# hs-256-expansion.net
KiCad netlist of a schematic drawn in EAGLE
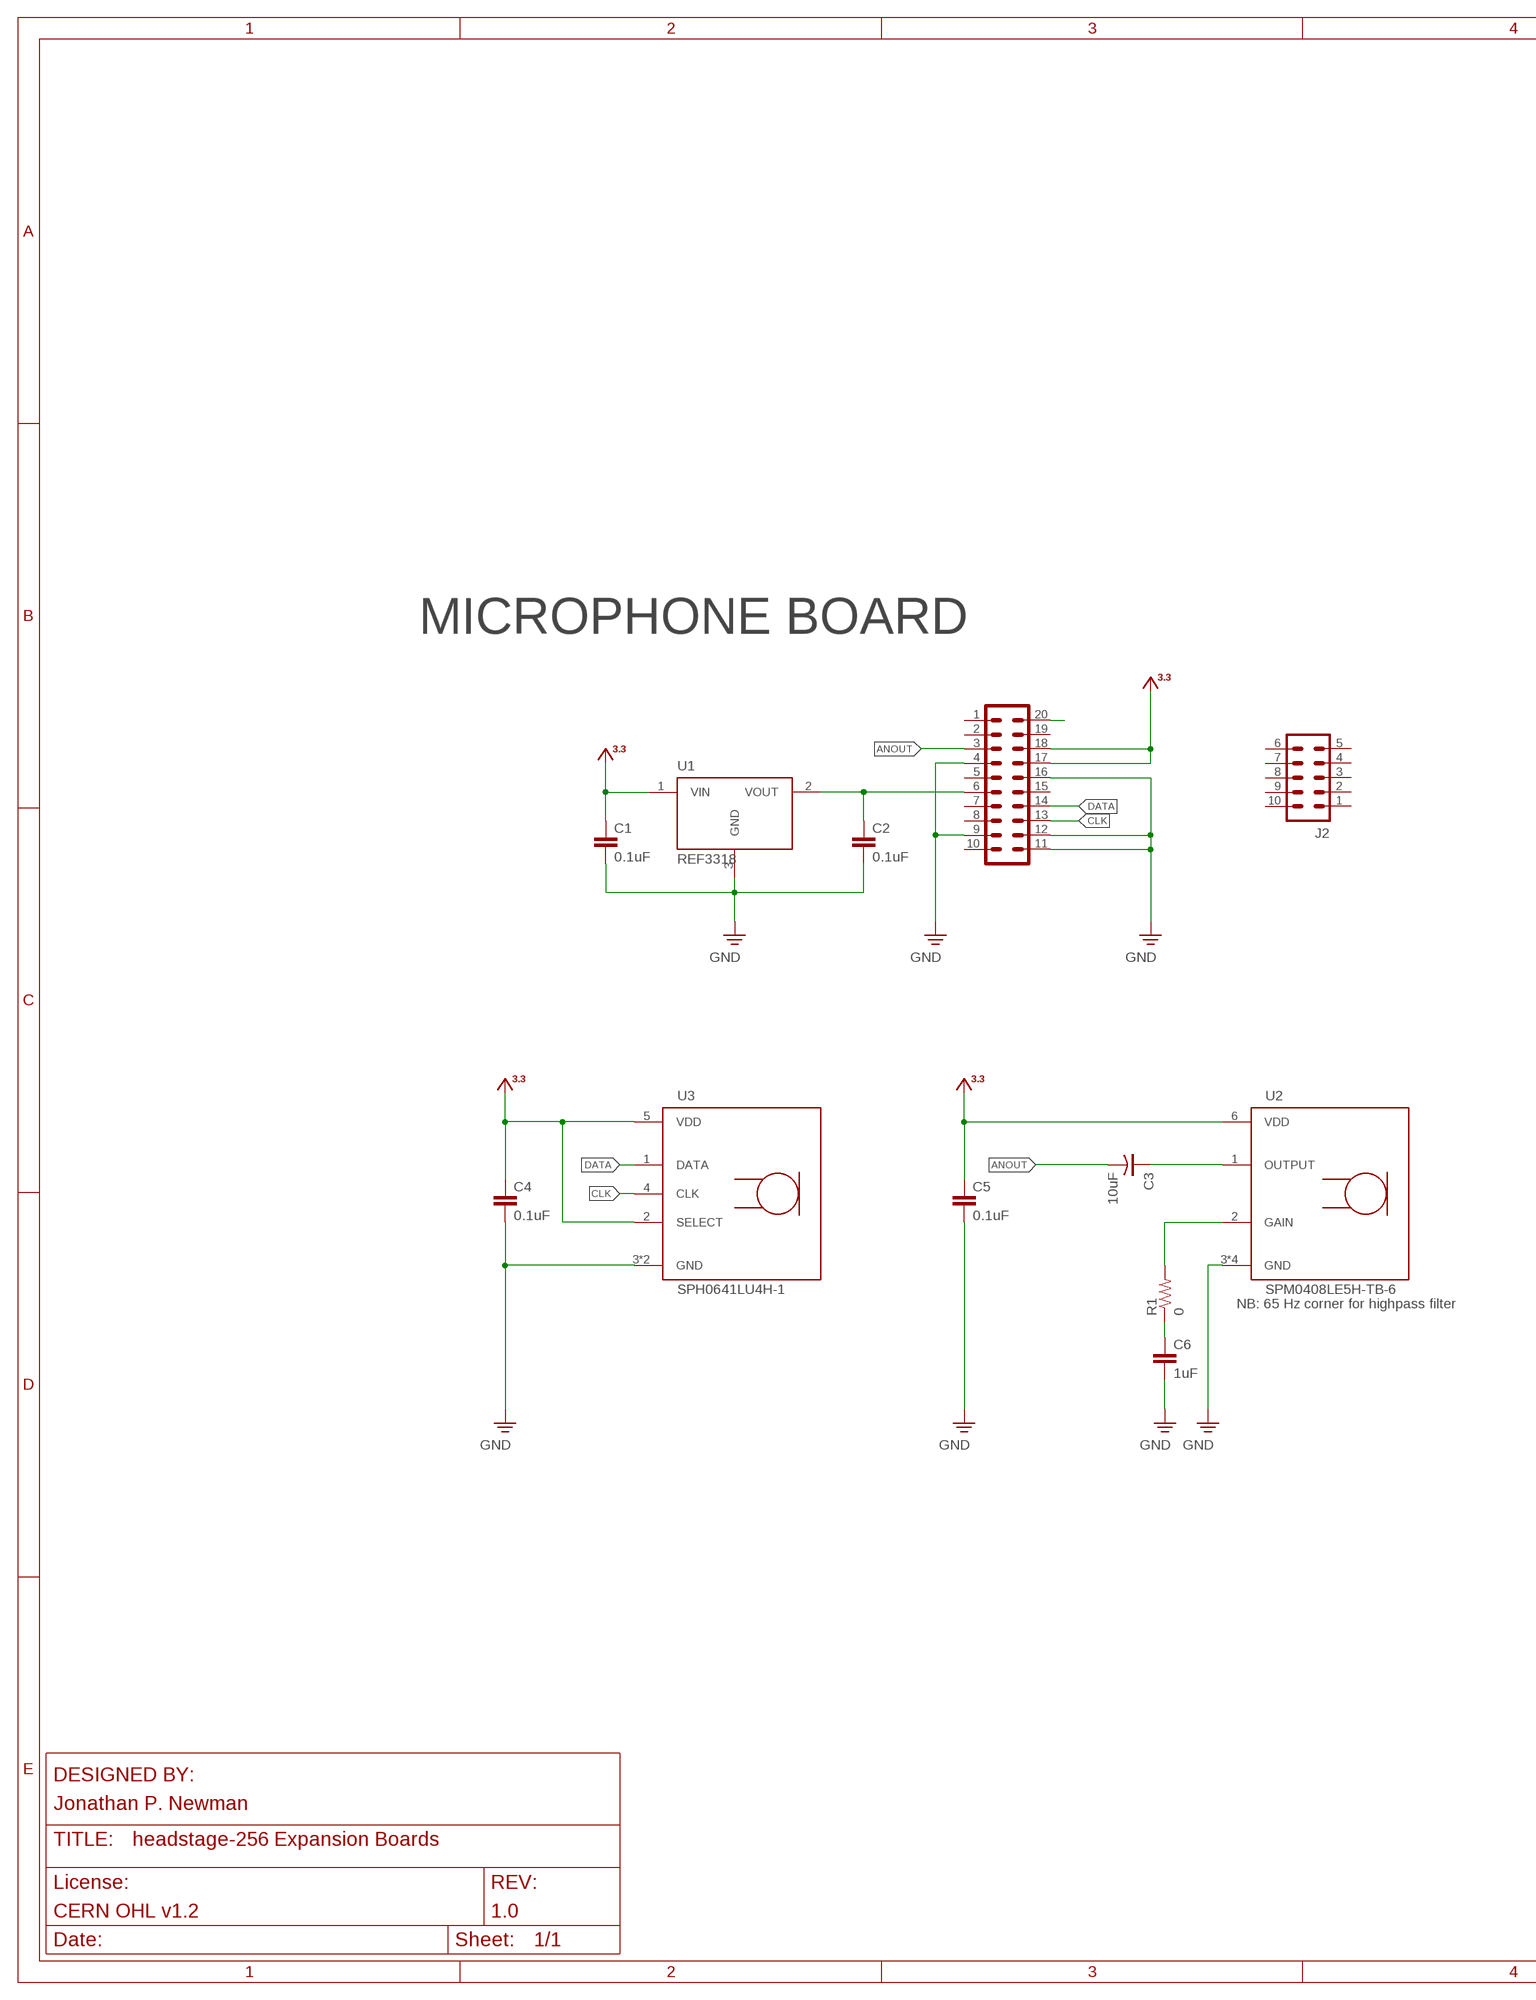
[diagram p0: schematic, sheet 1, part 1 of 2]
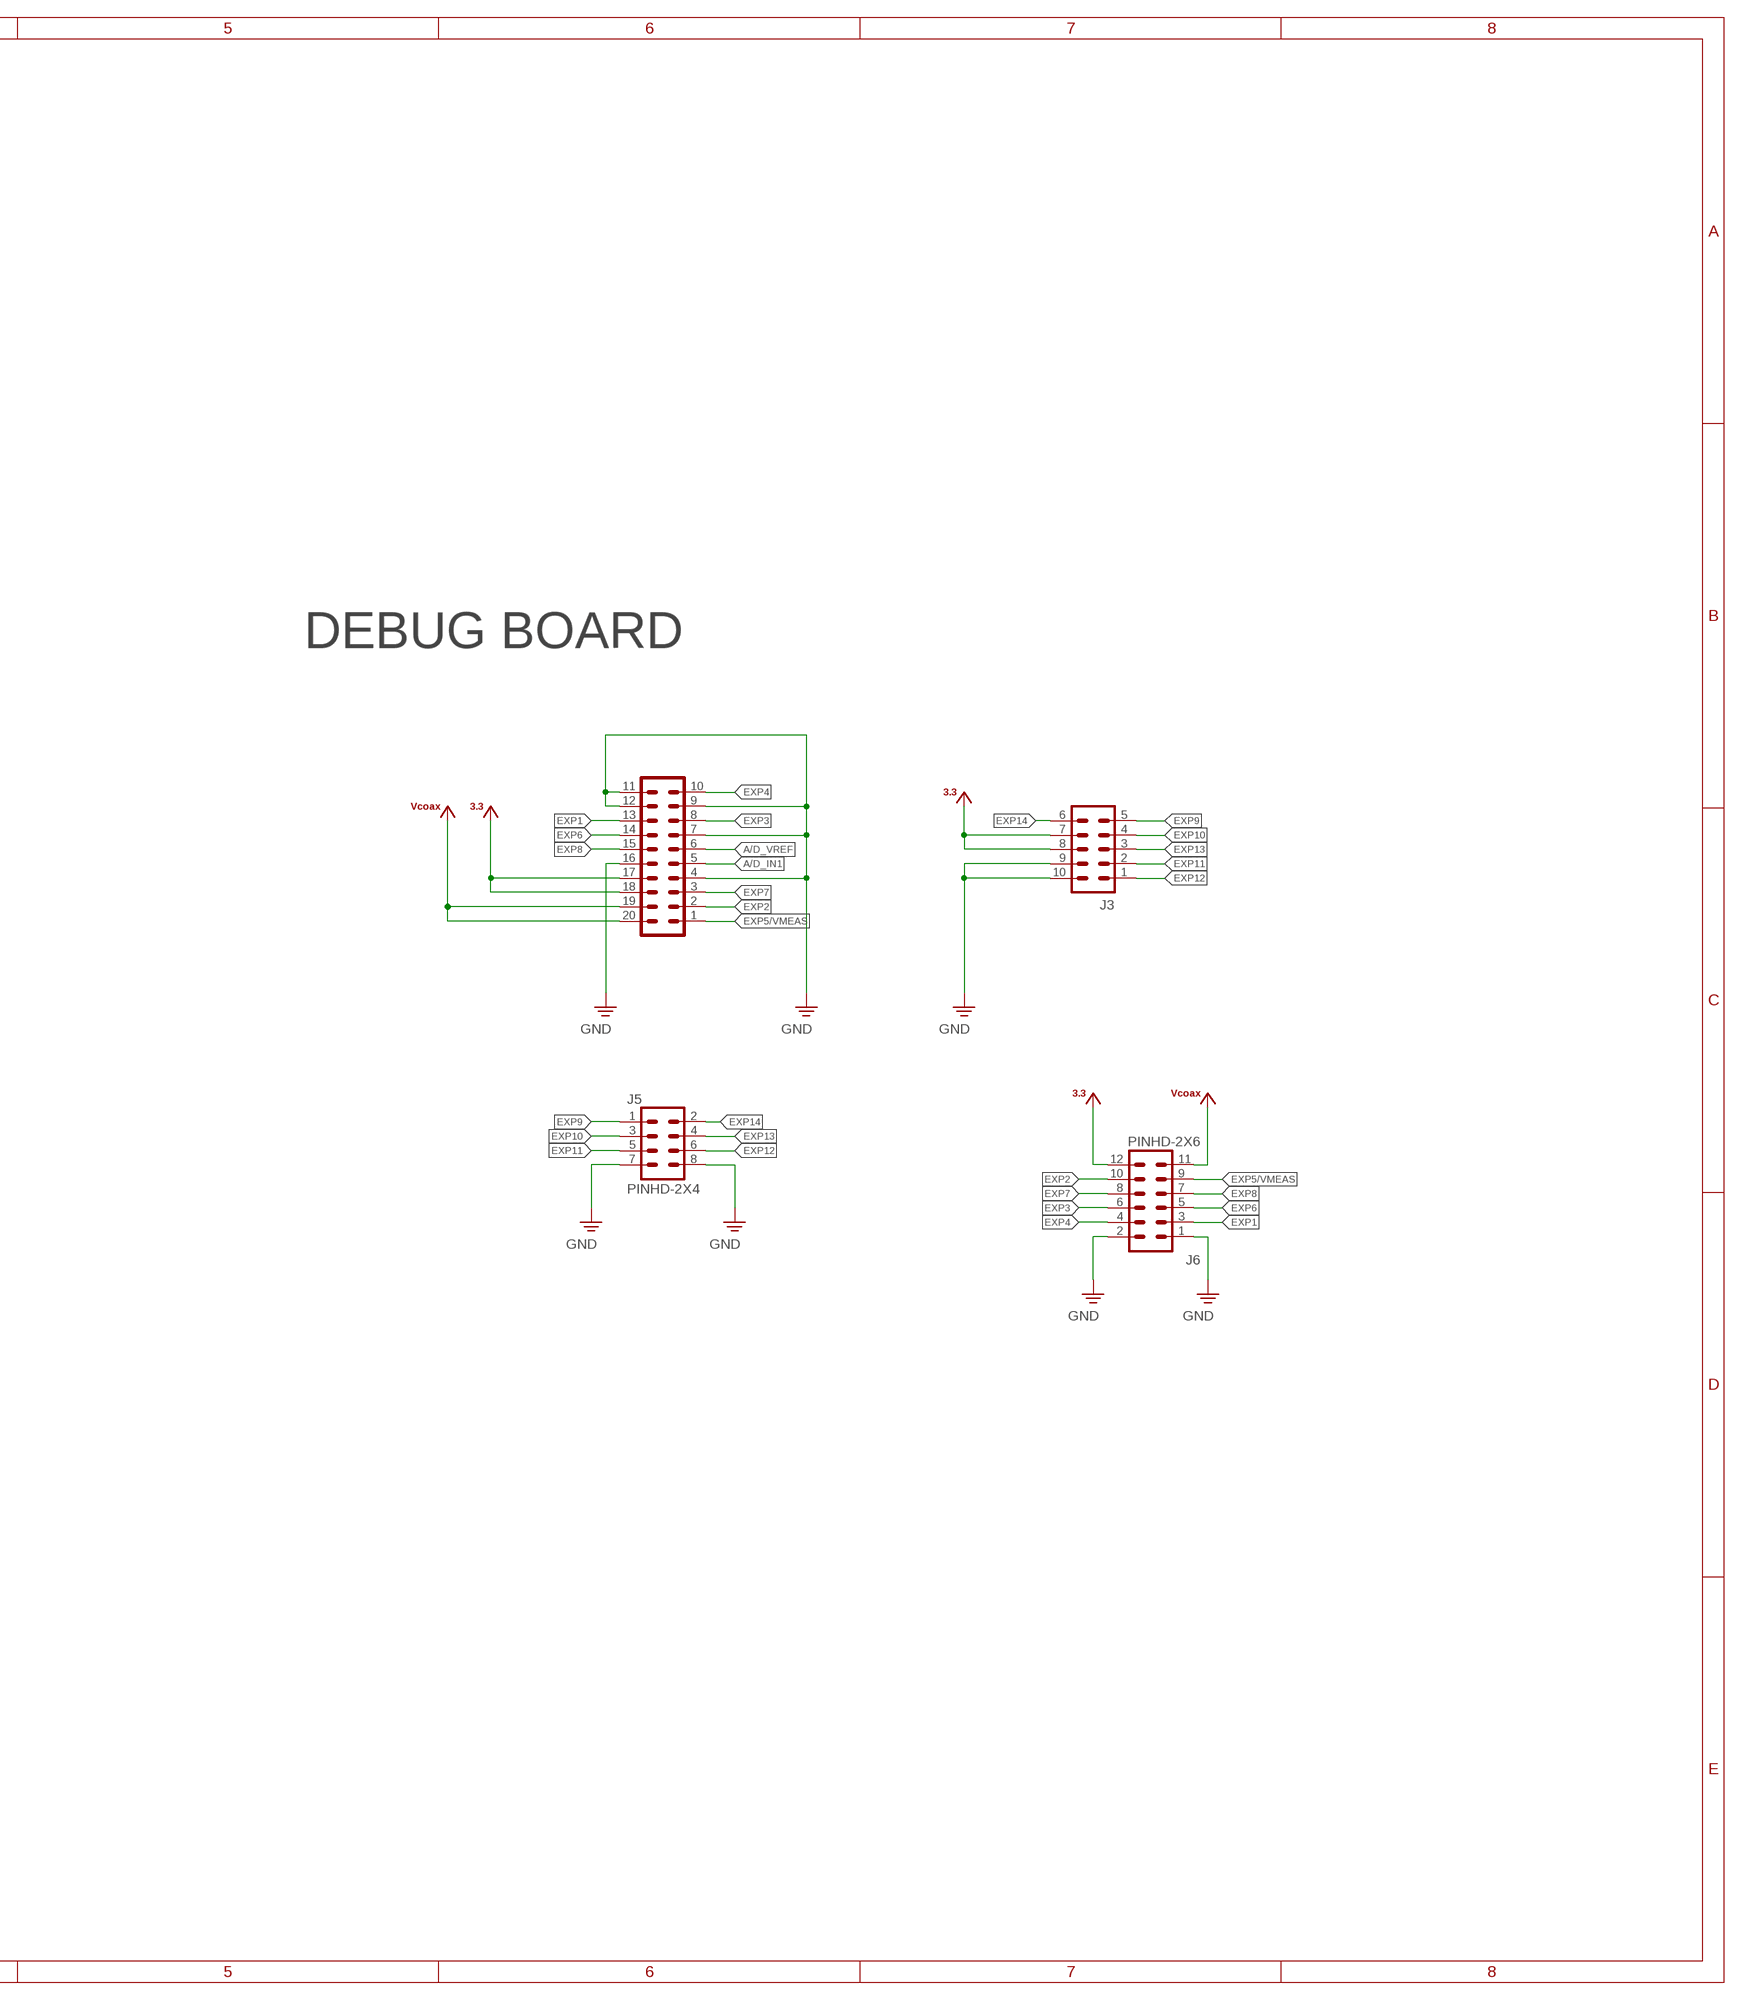
[diagram p1: schematic, sheet 1, part 2 of 2]

(export (version "E")
  (design (tool "Eeschema 10.0.6"))
  (components
    (comp (ref "C1")
      (value "0.1uF")
      (footprint "eagle-import:0402")
      (libsource (lib "eagle-import") (part "C_0402"))
    )
    (comp (ref "C2")
      (value "0.1uF")
      (footprint "eagle-import:0402")
      (libsource (lib "eagle-import") (part "C_0402"))
    )
    (comp (ref "C3")
      (value "10uF")
      (footprint "eagle-import:0805-POL")
      (libsource (lib "eagle-import") (part "C-POL_0805"))
    )
    (comp (ref "C4")
      (value "0.1uF")
      (footprint "eagle-import:0402")
      (libsource (lib "eagle-import") (part "C_0402"))
    )
    (comp (ref "C5")
      (value "0.1uF")
      (footprint "eagle-import:0402")
      (libsource (lib "eagle-import") (part "C_0402"))
    )
    (comp (ref "C6")
      (value "1uF")
      (footprint "eagle-import:0402")
      (libsource (lib "eagle-import") (part "C_0402"))
    )
    (comp (ref "J1")
      (value "PINHD-2X10_DF40-20REC")
      (footprint "eagle-import:DF40-20REC")
      (libsource (lib "eagle-import") (part "PINHD-2X10_DF40-20REC"))
    )
    (comp (ref "J2")
      (value "PINHD-2X5_DF40-REC")
      (footprint "eagle-import:DF40-10REC")
      (libsource (lib "eagle-import") (part "PINHD-2X5_DF40-REC"))
    )
    (comp (ref "J3")
      (value "PINHD-2X5_DF40-REC")
      (footprint "eagle-import:DF40-10REC")
      (libsource (lib "eagle-import") (part "PINHD-2X5_DF40-REC"))
    )
    (comp (ref "J4")
      (value "PINHD-2X10_DF40-20REC")
      (footprint "eagle-import:DF40-20REC")
      (libsource (lib "eagle-import") (part "PINHD-2X10_DF40-20REC"))
    )
    (comp (ref "J5")
      (value "PINHD-2X4")
      (footprint "eagle-import:2X04-BIG")
      (libsource (lib "eagle-import") (part "PINHD-2X4"))
    )
    (comp (ref "J6")
      (value "PINHD-2X6")
      (footprint "eagle-import:2X06-BIG")
      (libsource (lib "eagle-import") (part "PINHD-2X6"))
    )
    (comp (ref "R1")
      (value "0")
      (footprint "eagle-import:0402")
      (libsource (lib "eagle-import") (part "R_0402"))
    )
    (comp (ref "U1")
      (value "REF3318")
      (footprint "eagle-import:SOT23")
      (libsource (lib "eagle-import") (part "VREF_SOT"))
    )
    (comp (ref "U2")
      (value "SPM0408LE5H-TB-6")
      (footprint "eagle-import:KNOWLES-SPM")
      (libsource (lib "eagle-import") (part "MICROPHONE-AN_SPM"))
    )
    (comp (ref "U3")
      (value "SPH0641LU4H-1")
      (footprint "eagle-import:KNOWLES-SPH")
      (libsource (lib "eagle-import") (part "MICROPHONE-PCM_SPH"))
    )
  )
  (nets
    (net (code "1") (name "+3V3") (class "Default")
      (node (ref "C1") (pin "1") (pinfunction "1_1") (pintype "passive"))
      (node (ref "C4") (pin "1") (pinfunction "1_1") (pintype "passive"))
      (node (ref "C5") (pin "1") (pinfunction "1_1") (pintype "passive"))
      (node (ref "J1") (pin "17") (pinfunction "17_17") (pintype "bidirectional"))
      (node (ref "J1") (pin "18") (pinfunction "18_18") (pintype "bidirectional"))
      (node (ref "J3") (pin "7") (pinfunction "8_7") (pintype "passive"))
      (node (ref "J3") (pin "8") (pinfunction "6_8") (pintype "passive"))
      (node (ref "J4") (pin "17") (pinfunction "17_17") (pintype "bidirectional"))
      (node (ref "J4") (pin "18") (pinfunction "18_18") (pintype "bidirectional"))
      (node (ref "J6") (pin "12") (pinfunction "12_12") (pintype "passive"))
      (node (ref "U1") (pin "1") (pinfunction "VIN_1") (pintype "input"))
      (node (ref "U2") (pin "6") (pinfunction "VDD_6") (pintype "power_in"))
      (node (ref "U3") (pin "2") (pinfunction "SELECT_2") (pintype "input"))
      (node (ref "U3") (pin "5") (pinfunction "VDD_5") (pintype "bidirectional"))
    )
    (net (code "2") (name "+VCOAX") (class "Default")
      (node (ref "J4") (pin "19") (pinfunction "19_19") (pintype "bidirectional"))
      (node (ref "J4") (pin "20") (pinfunction "20_20") (pintype "bidirectional"))
      (node (ref "J6") (pin "11") (pinfunction "11_11") (pintype "passive"))
    )
    (net (code "3") (name "ANOUT") (class "Default")
      (node (ref "C3") (pin "C") (pinfunction "-_C") (pintype "passive"))
      (node (ref "J1") (pin "3") (pinfunction "3_3") (pintype "bidirectional"))
    )
    (net (code "4") (name "A{slash}D_IN1") (class "Default")
      (node (ref "J4") (pin "5") (pinfunction "5_5") (pintype "bidirectional"))
    )
    (net (code "5") (name "A{slash}D_VREF") (class "Default")
      (node (ref "J4") (pin "6") (pinfunction "6_6") (pintype "bidirectional"))
    )
    (net (code "6") (name "CLK") (class "Default")
      (node (ref "J1") (pin "13") (pinfunction "13_13") (pintype "bidirectional"))
      (node (ref "U3") (pin "4") (pinfunction "CLK_4") (pintype "input"))
    )
    (net (code "7") (name "DATA") (class "Default")
      (node (ref "J1") (pin "14") (pinfunction "14_14") (pintype "bidirectional"))
      (node (ref "U3") (pin "1") (pinfunction "DATA_1") (pintype "output"))
    )
    (net (code "8") (name "EXP1") (class "Default")
      (node (ref "J4") (pin "13") (pinfunction "13_13") (pintype "bidirectional"))
      (node (ref "J6") (pin "3") (pinfunction "3_3") (pintype "passive"))
    )
    (net (code "9") (name "EXP2") (class "Default")
      (node (ref "J4") (pin "2") (pinfunction "2_2") (pintype "bidirectional"))
      (node (ref "J6") (pin "10") (pinfunction "10_10") (pintype "passive"))
    )
    (net (code "10") (name "EXP3") (class "Default")
      (node (ref "J4") (pin "8") (pinfunction "8_8") (pintype "bidirectional"))
      (node (ref "J6") (pin "6") (pinfunction "6_6") (pintype "passive"))
    )
    (net (code "11") (name "EXP4") (class "Default")
      (node (ref "J4") (pin "10") (pinfunction "10_10") (pintype "bidirectional"))
      (node (ref "J6") (pin "4") (pinfunction "4_4") (pintype "passive"))
    )
    (net (code "12") (name "EXP5{slash}VMEAS") (class "Default")
      (node (ref "J4") (pin "1") (pinfunction "1_1") (pintype "bidirectional"))
      (node (ref "J6") (pin "9") (pinfunction "9_9") (pintype "passive"))
    )
    (net (code "13") (name "EXP6") (class "Default")
      (node (ref "J4") (pin "14") (pinfunction "14_14") (pintype "bidirectional"))
      (node (ref "J6") (pin "5") (pinfunction "5_5") (pintype "passive"))
    )
    (net (code "14") (name "EXP7") (class "Default")
      (node (ref "J4") (pin "3") (pinfunction "3_3") (pintype "bidirectional"))
      (node (ref "J6") (pin "8") (pinfunction "8_8") (pintype "passive"))
    )
    (net (code "15") (name "EXP8") (class "Default")
      (node (ref "J4") (pin "15") (pinfunction "15_15") (pintype "bidirectional"))
      (node (ref "J6") (pin "7") (pinfunction "7_7") (pintype "passive"))
    )
    (net (code "16") (name "EXP9") (class "Default")
      (node (ref "J3") (pin "5") (pinfunction "9_5") (pintype "passive"))
      (node (ref "J5") (pin "1") (pinfunction "1_1") (pintype "passive"))
    )
    (net (code "17") (name "EXP10") (class "Default")
      (node (ref "J3") (pin "4") (pinfunction "7_4") (pintype "passive"))
      (node (ref "J5") (pin "3") (pinfunction "3_3") (pintype "passive"))
    )
    (net (code "18") (name "EXP11") (class "Default")
      (node (ref "J3") (pin "2") (pinfunction "3_2") (pintype "passive"))
      (node (ref "J5") (pin "5") (pinfunction "5_5") (pintype "passive"))
    )
    (net (code "19") (name "EXP12") (class "Default")
      (node (ref "J3") (pin "1") (pinfunction "1_1") (pintype "passive"))
      (node (ref "J5") (pin "6") (pinfunction "6_6") (pintype "passive"))
    )
    (net (code "20") (name "EXP13") (class "Default")
      (node (ref "J3") (pin "3") (pinfunction "5_3") (pintype "passive"))
      (node (ref "J5") (pin "4") (pinfunction "4_4") (pintype "passive"))
    )
    (net (code "21") (name "EXP14") (class "Default")
      (node (ref "J3") (pin "6") (pinfunction "10_6") (pintype "passive"))
      (node (ref "J5") (pin "2") (pinfunction "2_2") (pintype "passive"))
    )
    (net (code "22") (name "GND") (class "Default")
      (node (ref "C1") (pin "2") (pinfunction "2_2") (pintype "passive"))
      (node (ref "C2") (pin "2") (pinfunction "2_2") (pintype "passive"))
      (node (ref "C4") (pin "2") (pinfunction "2_2") (pintype "passive"))
      (node (ref "C5") (pin "2") (pinfunction "2_2") (pintype "passive"))
      (node (ref "C6") (pin "2") (pinfunction "2_2") (pintype "passive"))
      (node (ref "J1") (pin "11") (pinfunction "11_11") (pintype "bidirectional"))
      (node (ref "J1") (pin "12") (pinfunction "12_12") (pintype "bidirectional"))
      (node (ref "J1") (pin "16") (pinfunction "16_16") (pintype "bidirectional"))
      (node (ref "J1") (pin "4") (pinfunction "4_4") (pintype "bidirectional"))
      (node (ref "J1") (pin "9") (pinfunction "9_9") (pintype "bidirectional"))
      (node (ref "J3") (pin "10") (pinfunction "2_10") (pintype "passive"))
      (node (ref "J3") (pin "9") (pinfunction "4_9") (pintype "passive"))
      (node (ref "J4") (pin "11") (pinfunction "11_11") (pintype "bidirectional"))
      (node (ref "J4") (pin "12") (pinfunction "12_12") (pintype "bidirectional"))
      (node (ref "J4") (pin "16") (pinfunction "16_16") (pintype "bidirectional"))
      (node (ref "J4") (pin "4") (pinfunction "4_4") (pintype "bidirectional"))
      (node (ref "J4") (pin "7") (pinfunction "7_7") (pintype "bidirectional"))
      (node (ref "J4") (pin "9") (pinfunction "9_9") (pintype "bidirectional"))
      (node (ref "J5") (pin "7") (pinfunction "7_7") (pintype "passive"))
      (node (ref "J5") (pin "8") (pinfunction "8_8") (pintype "passive"))
      (node (ref "J6") (pin "1") (pinfunction "1_1") (pintype "passive"))
      (node (ref "J6") (pin "2") (pinfunction "2_2") (pintype "passive"))
      (node (ref "U1") (pin "3") (pinfunction "GND_3") (pintype "power_in"))
      (node (ref "U2") (pin "3") (pinfunction "GND_3") (pintype "power_in"))
      (node (ref "U2") (pin "4") (pinfunction "GND_4") (pintype "power_in"))
      (node (ref "U2") (pin "5") (pinfunction "GND_5") (pintype "power_in"))
      (node (ref "U2") (pin "7") (pinfunction "GND_7") (pintype "power_in"))
      (node (ref "U3") (pin "3") (pinfunction "GND_3") (pintype "bidirectional"))
      (node (ref "U3") (pin "6") (pinfunction "GND_6") (pintype "bidirectional"))
    )
    (net (code "23") (name "Net-(C3-+)") (class "Default")
      (node (ref "C3") (pin "A") (pinfunction "+_A") (pintype "passive"))
      (node (ref "U2") (pin "1") (pinfunction "OUTPUT_1") (pintype "output"))
    )
    (net (code "24") (name "Net-(C6-Pad1)") (class "Default")
      (node (ref "C6") (pin "1") (pinfunction "1_1") (pintype "passive"))
      (node (ref "R1") (pin "1") (pinfunction "1_1") (pintype "passive"))
    )
    (net (code "25") (name "Net-(U1-VOUT)") (class "Default")
      (node (ref "C2") (pin "1") (pinfunction "1_1") (pintype "passive"))
      (node (ref "J1") (pin "6") (pinfunction "6_6") (pintype "bidirectional"))
      (node (ref "U1") (pin "2") (pinfunction "VOUT_2") (pintype "output"))
    )
    (net (code "26") (name "Net-(U2-GAIN)") (class "Default")
      (node (ref "R1") (pin "2") (pinfunction "2_2") (pintype "passive"))
      (node (ref "U2") (pin "2") (pinfunction "GAIN_2") (pintype "input"))
    )
    (net (code "27") (name "unconnected-(J1-Pad1)") (class "Default")
      (node (ref "J1") (pin "1") (pinfunction "1_1") (pintype "bidirectional"))
    )
    (net (code "28") (name "unconnected-(J1-Pad2)") (class "Default")
      (node (ref "J1") (pin "2") (pinfunction "2_2") (pintype "bidirectional"))
    )
    (net (code "29") (name "unconnected-(J1-Pad5)") (class "Default")
      (node (ref "J1") (pin "5") (pinfunction "5_5") (pintype "bidirectional"))
    )
    (net (code "30") (name "unconnected-(J1-Pad7)") (class "Default")
      (node (ref "J1") (pin "7") (pinfunction "7_7") (pintype "bidirectional"))
    )
    (net (code "31") (name "unconnected-(J1-Pad8)") (class "Default")
      (node (ref "J1") (pin "8") (pinfunction "8_8") (pintype "bidirectional"))
    )
    (net (code "32") (name "unconnected-(J1-Pad10)") (class "Default")
      (node (ref "J1") (pin "10") (pinfunction "10_10") (pintype "bidirectional"))
    )
    (net (code "33") (name "unconnected-(J1-Pad15)") (class "Default")
      (node (ref "J1") (pin "15") (pinfunction "15_15") (pintype "bidirectional"))
    )
    (net (code "34") (name "unconnected-(J1-Pad19)") (class "Default")
      (node (ref "J1") (pin "19") (pinfunction "19_19") (pintype "bidirectional"))
    )
    (net (code "35") (name "unconnected-(J1-Pad20)") (class "Default")
      (node (ref "J1") (pin "20") (pinfunction "20_20") (pintype "bidirectional"))
    )
    (net (code "36") (name "unconnected-(J2-2-Pad10)") (class "Default")
      (node (ref "J2") (pin "10") (pinfunction "2_10") (pintype "passive"))
    )
    (net (code "37") (name "unconnected-(J2-3-Pad2)") (class "Default")
      (node (ref "J2") (pin "2") (pinfunction "3_2") (pintype "passive"))
    )
    (net (code "38") (name "unconnected-(J2-4-Pad9)") (class "Default")
      (node (ref "J2") (pin "9") (pinfunction "4_9") (pintype "passive"))
    )
    (net (code "39") (name "unconnected-(J2-5-Pad3)") (class "Default")
      (node (ref "J2") (pin "3") (pinfunction "5_3") (pintype "passive"))
    )
    (net (code "40") (name "unconnected-(J2-6-Pad8)") (class "Default")
      (node (ref "J2") (pin "8") (pinfunction "6_8") (pintype "passive"))
    )
    (net (code "41") (name "unconnected-(J2-7-Pad4)") (class "Default")
      (node (ref "J2") (pin "4") (pinfunction "7_4") (pintype "passive"))
    )
    (net (code "42") (name "unconnected-(J2-8-Pad7)") (class "Default")
      (node (ref "J2") (pin "7") (pinfunction "8_7") (pintype "passive"))
    )
    (net (code "43") (name "unconnected-(J2-9-Pad5)") (class "Default")
      (node (ref "J2") (pin "5") (pinfunction "9_5") (pintype "passive"))
    )
    (net (code "44") (name "unconnected-(J2-10-Pad6)") (class "Default")
      (node (ref "J2") (pin "6") (pinfunction "10_6") (pintype "passive"))
    )
    (net (code "45") (name "unconnected-(J2-Pad1)") (class "Default")
      (node (ref "J2") (pin "1") (pinfunction "1_1") (pintype "passive"))
    )
  )
)
